# SensorNodePCB_set2_v2.net
KiCad netlist of a schematic drawn in EAGLE
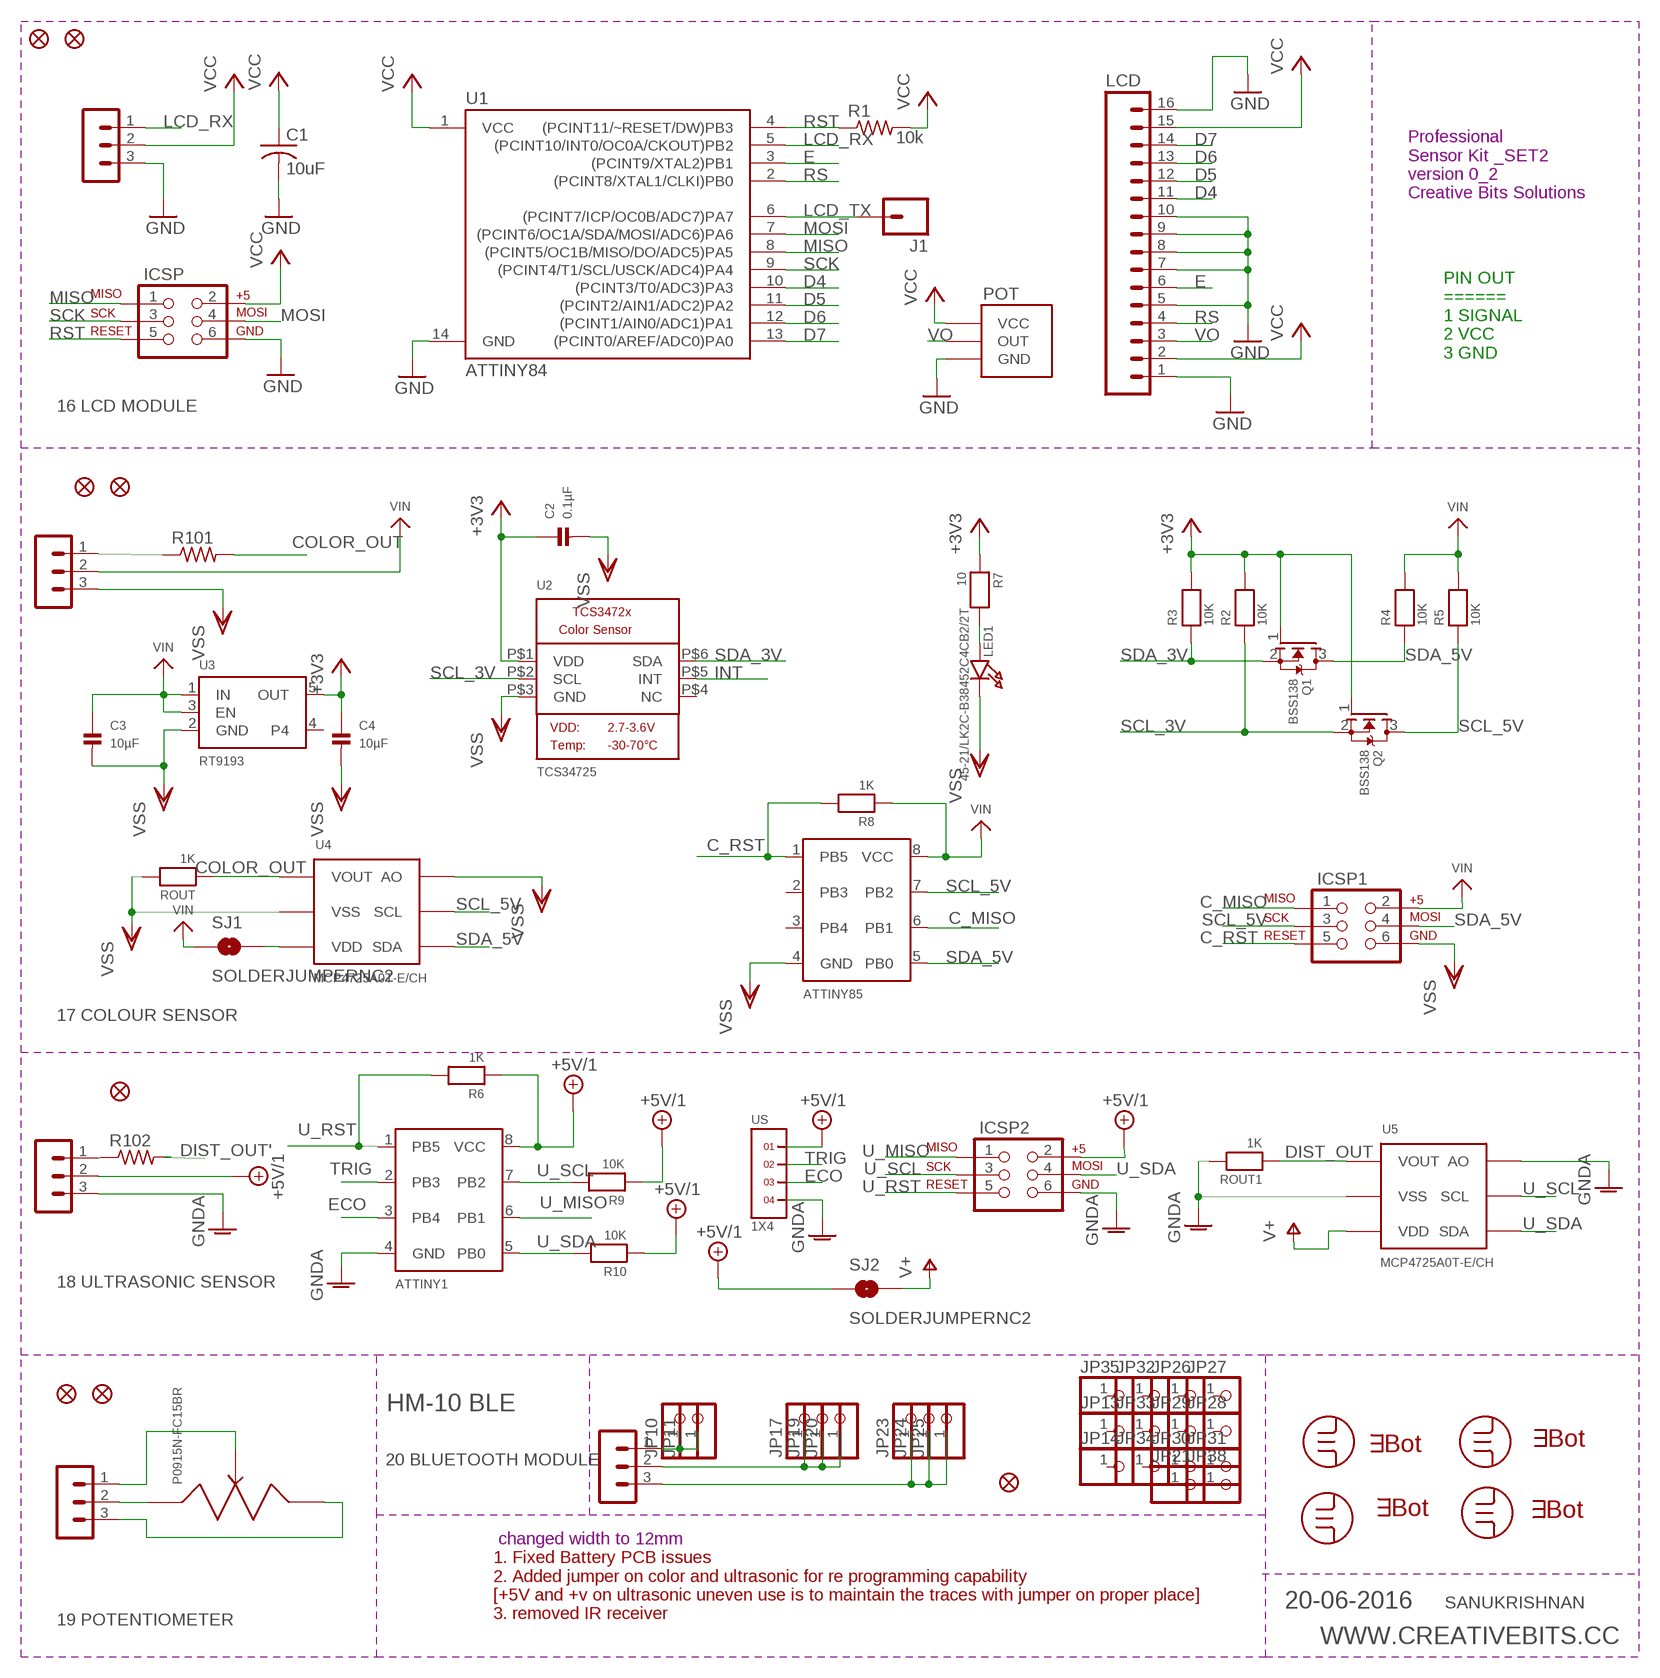
[diagram p0: schematic, sheet 1]

(export (version "E")
  (design (tool "Eeschema 10.0.6"))
  (components
    (comp (ref "ATTINY1")
      (value "ATTINY45")
      (footprint "eagle-import:SOIC8")
      (libsource (lib "eagle-import") (part "ATTINY45"))
    )
    (comp (ref "ATTINY85")
      (value "ATTINY45")
      (footprint "eagle-import:SOIC8")
      (libsource (lib "eagle-import") (part "ATTINY45"))
    )
    (comp (ref "C1")
      (value "10uF")
      (footprint "eagle-import:C1206")
      (libsource (lib "eagle-import") (part "C-USC1206"))
    )
    (comp (ref "C2")
      (value "0.1µF")
      (footprint "eagle-import:_0805")
      (libsource (lib "eagle-import") (part "CAP_CERAMIC_0805"))
    )
    (comp (ref "C3")
      (value "10µF")
      (footprint "eagle-import:_0805")
      (libsource (lib "eagle-import") (part "CAP_CERAMIC_0805"))
    )
    (comp (ref "C4")
      (value "10µF")
      (footprint "eagle-import:_0805")
      (libsource (lib "eagle-import") (part "CAP_CERAMIC_0805"))
    )
    (comp (ref "COLORSENSOR")
      (value "MA03-1")
      (footprint "eagle-import:MA03-1")
      (libsource (lib "eagle-import") (part "MA03-1"))
    )
    (comp (ref "ICSP")
      (value "AVR_SPI_PRG_6NS")
      (footprint "eagle-import:2X3-NS")
      (libsource (lib "eagle-import") (part "AVR_SPI_PRG_6NS"))
    )
    (comp (ref "ICSP1")
      (value "AVR_SPI_PRG_6NS")
      (footprint "eagle-import:2X3-NS")
      (libsource (lib "eagle-import") (part "AVR_SPI_PRG_6NS"))
    )
    (comp (ref "ICSP2")
      (value "AVR_SPI_PRG_6NS")
      (footprint "eagle-import:2X3-NS")
      (libsource (lib "eagle-import") (part "AVR_SPI_PRG_6NS"))
    )
    (comp (ref "J1")
      (value "M01NOSILK-KIT")
      (footprint "eagle-import:1X01NS-KIT")
      (libsource (lib "eagle-import") (part "M01NOSILK-KIT"))
    )
    (comp (ref "JP1")
      (value "FIDUCIAL1X2")
      (footprint "eagle-import:FIDUCIAL-1X2")
      (libsource (lib "eagle-import") (part "FIDUCIAL1X2"))
    )
    (comp (ref "JP2")
      (value "FIDUCIAL1X2")
      (footprint "eagle-import:FIDUCIAL-1X2")
      (libsource (lib "eagle-import") (part "FIDUCIAL1X2"))
    )
    (comp (ref "JP4")
      (value "FIDUCIAL1X2")
      (footprint "eagle-import:FIDUCIAL-1X2")
      (libsource (lib "eagle-import") (part "FIDUCIAL1X2"))
    )
    (comp (ref "JP6")
      (value "FIDUCIAL1X2")
      (footprint "eagle-import:FIDUCIAL-1X2")
      (libsource (lib "eagle-import") (part "FIDUCIAL1X2"))
    )
    (comp (ref "JP9")
      (value "FIDUCIAL1X2")
      (footprint "eagle-import:FIDUCIAL-1X2")
      (libsource (lib "eagle-import") (part "FIDUCIAL1X2"))
    )
    (comp (ref "JP10")
      (value "PINHD-1X1CB")
      (footprint "eagle-import:1X01-CLEANBIG")
      (libsource (lib "eagle-import") (part "PINHD-1X1CB"))
    )
    (comp (ref "JP11")
      (value "PINHD-1X1CB")
      (footprint "eagle-import:1X01-CLEANBIG")
      (libsource (lib "eagle-import") (part "PINHD-1X1CB"))
    )
    (comp (ref "JP12")
      (value "FIDUCIAL1X2")
      (footprint "eagle-import:FIDUCIAL-1X2")
      (libsource (lib "eagle-import") (part "FIDUCIAL1X2"))
    )
    (comp (ref "JP13")
      (value "PINHD-1X1CB")
      (footprint "eagle-import:1X01-CLEANBIG")
      (libsource (lib "eagle-import") (part "PINHD-1X1CB"))
    )
    (comp (ref "JP14")
      (value "PINHD-1X1CB")
      (footprint "eagle-import:1X01-CLEANBIG")
      (libsource (lib "eagle-import") (part "PINHD-1X1CB"))
    )
    (comp (ref "JP15")
      (value "FIDUCIAL1X2")
      (footprint "eagle-import:FIDUCIAL-1X2")
      (libsource (lib "eagle-import") (part "FIDUCIAL1X2"))
    )
    (comp (ref "JP17")
      (value "PINHD-1X1CB")
      (footprint "eagle-import:1X01-CLEANBIG")
      (libsource (lib "eagle-import") (part "PINHD-1X1CB"))
    )
    (comp (ref "JP18")
      (value "FIDUCIAL1X2")
      (footprint "eagle-import:FIDUCIAL-1X2")
      (libsource (lib "eagle-import") (part "FIDUCIAL1X2"))
    )
    (comp (ref "JP19")
      (value "PINHD-1X1CB")
      (footprint "eagle-import:1X01-CLEANBIG")
      (libsource (lib "eagle-import") (part "PINHD-1X1CB"))
    )
    (comp (ref "JP20")
      (value "PINHD-1X1CB")
      (footprint "eagle-import:1X01-CLEANBIG")
      (libsource (lib "eagle-import") (part "PINHD-1X1CB"))
    )
    (comp (ref "JP21")
      (value "PINHD-1X1CB")
      (footprint "eagle-import:1X01-CLEANBIG")
      (libsource (lib "eagle-import") (part "PINHD-1X1CB"))
    )
    (comp (ref "JP23")
      (value "PINHD-1X1CB")
      (footprint "eagle-import:1X01-CLEANBIG")
      (libsource (lib "eagle-import") (part "PINHD-1X1CB"))
    )
    (comp (ref "JP24")
      (value "PINHD-1X1CB")
      (footprint "eagle-import:1X01-CLEANBIG")
      (libsource (lib "eagle-import") (part "PINHD-1X1CB"))
    )
    (comp (ref "JP25")
      (value "PINHD-1X1CB")
      (footprint "eagle-import:1X01-CLEANBIG")
      (libsource (lib "eagle-import") (part "PINHD-1X1CB"))
    )
    (comp (ref "JP26")
      (value "PINHD-1X1CB")
      (footprint "eagle-import:1X01-CLEANBIG")
      (libsource (lib "eagle-import") (part "PINHD-1X1CB"))
    )
    (comp (ref "JP27")
      (value "PINHD-1X1CB")
      (footprint "eagle-import:1X01-CLEANBIG")
      (libsource (lib "eagle-import") (part "PINHD-1X1CB"))
    )
    (comp (ref "JP28")
      (value "PINHD-1X1CB")
      (footprint "eagle-import:1X01-CLEANBIG")
      (libsource (lib "eagle-import") (part "PINHD-1X1CB"))
    )
    (comp (ref "JP29")
      (value "PINHD-1X1CB")
      (footprint "eagle-import:1X01-CLEANBIG")
      (libsource (lib "eagle-import") (part "PINHD-1X1CB"))
    )
    (comp (ref "JP30")
      (value "PINHD-1X1CB")
      (footprint "eagle-import:1X01-CLEANBIG")
      (libsource (lib "eagle-import") (part "PINHD-1X1CB"))
    )
    (comp (ref "JP31")
      (value "PINHD-1X1CB")
      (footprint "eagle-import:1X01-CLEANBIG")
      (libsource (lib "eagle-import") (part "PINHD-1X1CB"))
    )
    (comp (ref "JP32")
      (value "PINHD-1X1CB")
      (footprint "eagle-import:1X01-CLEANBIG")
      (libsource (lib "eagle-import") (part "PINHD-1X1CB"))
    )
    (comp (ref "JP33")
      (value "PINHD-1X1CB")
      (footprint "eagle-import:1X01-CLEANBIG")
      (libsource (lib "eagle-import") (part "PINHD-1X1CB"))
    )
    (comp (ref "JP34")
      (value "PINHD-1X1CB")
      (footprint "eagle-import:1X01-CLEANBIG")
      (libsource (lib "eagle-import") (part "PINHD-1X1CB"))
    )
    (comp (ref "JP35")
      (value "PINHD-1X1CB")
      (footprint "eagle-import:1X01-CLEANBIG")
      (libsource (lib "eagle-import") (part "PINHD-1X1CB"))
    )
    (comp (ref "JP38")
      (value "PINHD-1X1CB")
      (footprint "eagle-import:1X01-CLEANBIG")
      (libsource (lib "eagle-import") (part "PINHD-1X1CB"))
    )
    (comp (ref "LCD")
      (value "M16LONGPADS")
      (footprint "eagle-import:1X16_LONGPADS")
      (libsource (lib "eagle-import") (part "M16LONGPADS"))
    )
    (comp (ref "LCD_NODE")
      (value "MA03-1")
      (footprint "eagle-import:MA03-1")
      (libsource (lib "eagle-import") (part "MA03-1"))
    )
    (comp (ref "LED1")
      (value "45-21/LK2C-B38452C4CB2/2T")
      (footprint "eagle-import:EVERLIGHT_45-21")
      (libsource (lib "eagle-import") (part "LEDEV45-21"))
    )
    (comp (ref "POT")
      (value "TRIMMER_EVN")
      (footprint "eagle-import:TRIMMER_EVN")
      (libsource (lib "eagle-import") (part "TRIMMER_EVN"))
    )
    (comp (ref "POT1")
      (value "P0915N-FC15BR")
      (footprint "eagle-import:P0915N-FC15BR")
      (libsource (lib "eagle-import") (part "P0915N-FC15BR"))
    )
    (comp (ref "POTENTIOMETER")
      (value "MA03-1")
      (footprint "eagle-import:MA03-1")
      (libsource (lib "eagle-import") (part "MA03-1"))
    )
    (comp (ref "Q1")
      (value "BSS138")
      (footprint "eagle-import:SOT23-WIDE")
      (libsource (lib "eagle-import") (part "MOSFET-NWIDE"))
    )
    (comp (ref "Q2")
      (value "BSS138")
      (footprint "eagle-import:SOT23-WIDE")
      (libsource (lib "eagle-import") (part "MOSFET-NWIDE"))
    )
    (comp (ref "R1")
      (value "10k")
      (footprint "eagle-import:M0805")
      (libsource (lib "eagle-import") (part "R-US_M0805"))
    )
    (comp (ref "R2")
      (value "10K")
      (footprint "eagle-import:_0805")
      (libsource (lib "eagle-import") (part "RESISTOR_0805"))
    )
    (comp (ref "R3")
      (value "10K")
      (footprint "eagle-import:_0805")
      (libsource (lib "eagle-import") (part "RESISTOR_0805"))
    )
    (comp (ref "R4")
      (value "10K")
      (footprint "eagle-import:_0805")
      (libsource (lib "eagle-import") (part "RESISTOR_0805"))
    )
    (comp (ref "R5")
      (value "10K")
      (footprint "eagle-import:_0805")
      (libsource (lib "eagle-import") (part "RESISTOR_0805"))
    )
    (comp (ref "R6")
      (value "1K")
      (footprint "eagle-import:_0805")
      (libsource (lib "eagle-import") (part "RESISTOR_0805"))
    )
    (comp (ref "R7")
      (value "10")
      (footprint "eagle-import:_0805")
      (libsource (lib "eagle-import") (part "RESISTOR_0805"))
    )
    (comp (ref "R8")
      (value "1K")
      (footprint "eagle-import:_0805")
      (libsource (lib "eagle-import") (part "RESISTOR_0805"))
    )
    (comp (ref "R9")
      (value "10K")
      (footprint "eagle-import:_0805")
      (libsource (lib "eagle-import") (part "RESISTOR_0805"))
    )
    (comp (ref "R10")
      (value "10K")
      (footprint "eagle-import:_0805")
      (libsource (lib "eagle-import") (part "RESISTOR_0805"))
    )
    (comp (ref "R101")
      (value "R-US_M0805")
      (footprint "eagle-import:M0805")
      (libsource (lib "eagle-import") (part "R-US_M0805"))
    )
    (comp (ref "R102")
      (value "R-US_M0805")
      (footprint "eagle-import:M0805")
      (libsource (lib "eagle-import") (part "R-US_M0805"))
    )
    (comp (ref "ROUT")
      (value "1K")
      (footprint "eagle-import:_0805")
      (libsource (lib "eagle-import") (part "RESISTOR_0805"))
    )
    (comp (ref "ROUT1")
      (value "1K")
      (footprint "eagle-import:_0805")
      (libsource (lib "eagle-import") (part "RESISTOR_0805"))
    )
    (comp (ref "SJ1")
      (value "SOLDERJUMPERNC2")
      (footprint "eagle-import:SJ_2S-NOTRACE")
      (libsource (lib "eagle-import") (part "SOLDERJUMPERNC2"))
    )
    (comp (ref "SJ2")
      (value "SOLDERJUMPERNC2")
      (footprint "eagle-import:SJ_2S-NOTRACE")
      (libsource (lib "eagle-import") (part "SOLDERJUMPERNC2"))
    )
    (comp (ref "U$30")
      (value "EBOT_LOGO_6MMX6MM")
      (footprint "eagle-import:EBOT_6MMX6MM")
      (libsource (lib "eagle-import") (part "EBOT_LOGO_6MMX6MM"))
    )
    (comp (ref "U$32")
      (value "EBOT_LOGO_6MMX6MM")
      (footprint "eagle-import:EBOT_6MMX6MM")
      (libsource (lib "eagle-import") (part "EBOT_LOGO_6MMX6MM"))
    )
    (comp (ref "U$33")
      (value "EBOT_LOGO_6MMX6MM")
      (footprint "eagle-import:EBOT_6MMX6MM")
      (libsource (lib "eagle-import") (part "EBOT_LOGO_6MMX6MM"))
    )
    (comp (ref "U$34")
      (value "EBOT_LOGO_6MMX6MM")
      (footprint "eagle-import:EBOT_6MMX6MM")
      (libsource (lib "eagle-import") (part "EBOT_LOGO_6MMX6MM"))
    )
    (comp (ref "U$35")
      (value "EBOT_NAME_6MM")
      (footprint "eagle-import:EBOT_NAME_6MM")
      (libsource (lib "eagle-import") (part "EBOT_NAME_6MM"))
    )
    (comp (ref "U$37")
      (value "EBOT_NAME_6MM")
      (footprint "eagle-import:EBOT_NAME_6MM")
      (libsource (lib "eagle-import") (part "EBOT_NAME_6MM"))
    )
    (comp (ref "U$38")
      (value "EBOT_NAME_6MM")
      (footprint "eagle-import:EBOT_NAME_6MM")
      (libsource (lib "eagle-import") (part "EBOT_NAME_6MM"))
    )
    (comp (ref "U$39")
      (value "EBOT_NAME_6MM")
      (footprint "eagle-import:EBOT_NAME_6MM")
      (libsource (lib "eagle-import") (part "EBOT_NAME_6MM"))
    )
    (comp (ref "U1")
      (value "ATTINY84")
      (footprint "eagle-import:SO14")
      (libsource (lib "eagle-import") (part "ATTINY84"))
    )
    (comp (ref "U2")
      (value "TCS34725")
      (footprint "eagle-import:TCS3472_FN6")
      (libsource (lib "eagle-import") (part "LIGHT_TCS3472"))
    )
    (comp (ref "U3")
      (value "RT9193")
      (footprint "eagle-import:SOT23-5")
      (libsource (lib "eagle-import") (part "VREG_SOT23-5"))
    )
    (comp (ref "U4")
      (value "MCP4725")
      (footprint "eagle-import:MCP4725")
      (libsource (lib "eagle-import") (part "MCP4725"))
    )
    (comp (ref "U5")
      (value "MCP4725")
      (footprint "eagle-import:MCP4725")
      (libsource (lib "eagle-import") (part "MCP4725"))
    )
    (comp (ref "ULTRASONICSENSOR")
      (value "MA03-1")
      (footprint "eagle-import:MA03-1")
      (libsource (lib "eagle-import") (part "MA03-1"))
    )
    (comp (ref "ULTRASONICSENSOR1")
      (value "MA03-1")
      (footprint "eagle-import:MA03-1")
      (libsource (lib "eagle-import") (part "MA03-1"))
    )
    (comp (ref "US")
      (value "1X4")
      (footprint "eagle-import:1X4")
      (libsource (lib "eagle-import") (part "1X4"))
    )
  )
  (nets
    (net (code "1") (name "+3V3") (class "Default")
      (node (ref "C2") (pin "1") (pinfunction "P$1_1") (pintype "passive"))
      (node (ref "C4") (pin "1") (pinfunction "P$1_1") (pintype "passive"))
      (node (ref "Q1") (pin "1") (pinfunction "G_1") (pintype "bidirectional"))
      (node (ref "Q2") (pin "1") (pinfunction "G_1") (pintype "bidirectional"))
      (node (ref "R2") (pin "2") (pinfunction "2_2") (pintype "passive"))
      (node (ref "R3") (pin "2") (pinfunction "2_2") (pintype "passive"))
      (node (ref "R7") (pin "1") (pinfunction "1_1") (pintype "passive"))
      (node (ref "U2") (pin "P$1") (pinfunction "VDD_P$1") (pintype "power_in"))
      (node (ref "U3") (pin "5") (pinfunction "OUT_5") (pintype "bidirectional"))
    )
    (net (code "2") (name "+5V{slash}1") (class "Default")
      (node (ref "ATTINY1") (pin "8") (pinfunction "VCC_8") (pintype "power_in"))
      (node (ref "ICSP2") (pin "2") (pinfunction "2_2") (pintype "passive"))
      (node (ref "R10") (pin "1") (pinfunction "1_1") (pintype "passive"))
      (node (ref "R6") (pin "1") (pinfunction "1_1") (pintype "passive"))
      (node (ref "R9") (pin "1") (pinfunction "1_1") (pintype "passive"))
      (node (ref "SJ2") (pin "1") (pinfunction "1_1") (pintype "passive"))
      (node (ref "ULTRASONICSENSOR") (pin "2") (pinfunction "2_2") (pintype "passive"))
      (node (ref "US") (pin "1") (pinfunction "1_1") (pintype "bidirectional"))
    )
    (net (code "3") (name "/COLOR_OUT") (class "Default")
      (node (ref "R101") (pin "2") (pinfunction "2_2") (pintype "passive"))
      (node (ref "ROUT") (pin "1") (pinfunction "1_1") (pintype "passive"))
      (node (ref "U4") (pin "P$1") (pinfunction "VOUT_P$1") (pintype "bidirectional"))
    )
    (net (code "4") (name "/C_MISO") (class "Default")
      (node (ref "ATTINY85") (pin "6") (pinfunction "PB1_6") (pintype "bidirectional"))
      (node (ref "ICSP1") (pin "1") (pinfunction "1_1") (pintype "passive"))
    )
    (net (code "5") (name "/C_RST") (class "Default")
      (node (ref "ATTINY85") (pin "1") (pinfunction "PB5_1") (pintype "bidirectional"))
      (node (ref "ICSP1") (pin "5") (pinfunction "5_5") (pintype "passive"))
      (node (ref "R8") (pin "2") (pinfunction "2_2") (pintype "passive"))
    )
    (net (code "6") (name "/D4") (class "Default")
      (node (ref "LCD") (pin "11") (pinfunction "11_11") (pintype "passive"))
      (node (ref "U1") (pin "10") (pinfunction "(PCINT3/T0/ADC3)PA3_10") (pintype "bidirectional"))
    )
    (net (code "7") (name "/D5") (class "Default")
      (node (ref "LCD") (pin "12") (pinfunction "12_12") (pintype "passive"))
      (node (ref "U1") (pin "11") (pinfunction "(PCINT2/AIN1/ADC2)PA2_11") (pintype "bidirectional"))
    )
    (net (code "8") (name "/D6") (class "Default")
      (node (ref "LCD") (pin "13") (pinfunction "13_13") (pintype "passive"))
      (node (ref "U1") (pin "12") (pinfunction "(PCINT1/AIN0/ADC1)PA1_12") (pintype "bidirectional"))
    )
    (net (code "9") (name "/D7") (class "Default")
      (node (ref "LCD") (pin "14") (pinfunction "14_14") (pintype "passive"))
      (node (ref "U1") (pin "13") (pinfunction "(PCINT0/AREF/ADC0)PA0_13") (pintype "bidirectional"))
    )
    (net (code "10") (name "/DIST_OUT") (class "Default")
      (node (ref "R102") (pin "2") (pinfunction "2_2") (pintype "passive"))
      (node (ref "ROUT1") (pin "1") (pinfunction "1_1") (pintype "passive"))
      (node (ref "U5") (pin "P$1") (pinfunction "VOUT_P$1") (pintype "bidirectional"))
    )
    (net (code "11") (name "/DIST_OUT'") (class "Default")
      (node (ref "R102") (pin "1") (pinfunction "1_1") (pintype "passive"))
      (node (ref "ULTRASONICSENSOR") (pin "1") (pinfunction "1_1") (pintype "passive"))
    )
    (net (code "12") (name "/E") (class "Default")
      (node (ref "LCD") (pin "6") (pinfunction "6_6") (pintype "passive"))
      (node (ref "U1") (pin "3") (pinfunction "(PCINT9/XTAL2)PB1_3") (pintype "bidirectional"))
    )
    (net (code "13") (name "/ECO") (class "Default")
      (node (ref "ATTINY1") (pin "3") (pinfunction "PB4_3") (pintype "bidirectional"))
      (node (ref "US") (pin "3") (pinfunction "3_3") (pintype "bidirectional"))
    )
    (net (code "14") (name "/INT") (class "Default")
      (node (ref "U2") (pin "P$5") (pinfunction "INT_P$5") (pintype "output"))
    )
    (net (code "15") (name "/LCD_RX") (class "Default")
      (node (ref "LCD_NODE") (pin "1") (pinfunction "1_1") (pintype "passive"))
      (node (ref "U1") (pin "5") (pinfunction "(PCINT10/INT0/OC0A/CKOUT)PB2_5") (pintype "bidirectional"))
    )
    (net (code "16") (name "/LCD_TX") (class "Default")
      (node (ref "J1") (pin "1") (pinfunction "1_1") (pintype "passive"))
      (node (ref "U1") (pin "6") (pinfunction "(PCINT7/ICP/OC0B/ADC7)PA7_6") (pintype "bidirectional"))
    )
    (net (code "17") (name "/MISO") (class "Default")
      (node (ref "ICSP") (pin "1") (pinfunction "1_1") (pintype "passive"))
      (node (ref "U1") (pin "8") (pinfunction "(PCINT5/OC1B/MISO/DO/ADC5)PA5_8") (pintype "bidirectional"))
    )
    (net (code "18") (name "/MOSI") (class "Default")
      (node (ref "ICSP") (pin "4") (pinfunction "4_4") (pintype "passive"))
      (node (ref "U1") (pin "7") (pinfunction "(PCINT6/OC1A/SDA/MOSI/ADC6)PA6_7") (pintype "bidirectional"))
    )
    (net (code "19") (name "/RS") (class "Default")
      (node (ref "LCD") (pin "4") (pinfunction "4_4") (pintype "passive"))
      (node (ref "U1") (pin "2") (pinfunction "(PCINT8/XTAL1/CLKI)PB0_2") (pintype "bidirectional"))
    )
    (net (code "20") (name "/RST") (class "Default")
      (node (ref "ICSP") (pin "5") (pinfunction "5_5") (pintype "passive"))
      (node (ref "R1") (pin "1") (pinfunction "1_1") (pintype "passive"))
      (node (ref "U1") (pin "4") (pinfunction "(PCINT11/~{RESET/DW})PB3_4") (pintype "bidirectional"))
    )
    (net (code "21") (name "/SCK") (class "Default")
      (node (ref "ICSP") (pin "3") (pinfunction "3_3") (pintype "passive"))
      (node (ref "U1") (pin "9") (pinfunction "(PCINT4/T1/SCL/USCK/ADC4)PA4_9") (pintype "bidirectional"))
    )
    (net (code "22") (name "/SCL_3V") (class "Default")
      (node (ref "Q2") (pin "2") (pinfunction "S_2") (pintype "bidirectional"))
      (node (ref "R2") (pin "1") (pinfunction "1_1") (pintype "passive"))
      (node (ref "U2") (pin "P$2") (pinfunction "SCL_P$2") (pintype "bidirectional"))
    )
    (net (code "23") (name "/SCL_5V") (class "Default")
      (node (ref "ATTINY85") (pin "7") (pinfunction "PB2_7") (pintype "bidirectional"))
      (node (ref "ICSP1") (pin "3") (pinfunction "3_3") (pintype "passive"))
      (node (ref "Q2") (pin "3") (pinfunction "D_3") (pintype "bidirectional"))
      (node (ref "R5") (pin "1") (pinfunction "1_1") (pintype "passive"))
      (node (ref "U4") (pin "P$5") (pinfunction "SCL_P$5") (pintype "bidirectional"))
    )
    (net (code "24") (name "/SDA_3V") (class "Default")
      (node (ref "Q1") (pin "2") (pinfunction "S_2") (pintype "bidirectional"))
      (node (ref "R3") (pin "1") (pinfunction "1_1") (pintype "passive"))
      (node (ref "U2") (pin "P$6") (pinfunction "SDA_P$6") (pintype "bidirectional"))
    )
    (net (code "25") (name "/SDA_5V") (class "Default")
      (node (ref "ATTINY85") (pin "5") (pinfunction "PB0_5") (pintype "bidirectional"))
      (node (ref "ICSP1") (pin "4") (pinfunction "4_4") (pintype "passive"))
      (node (ref "Q1") (pin "3") (pinfunction "D_3") (pintype "bidirectional"))
      (node (ref "R4") (pin "1") (pinfunction "1_1") (pintype "passive"))
      (node (ref "U4") (pin "P$4") (pinfunction "SDA_P$4") (pintype "bidirectional"))
    )
    (net (code "26") (name "/TRIG") (class "Default")
      (node (ref "ATTINY1") (pin "2") (pinfunction "PB3_2") (pintype "bidirectional"))
      (node (ref "US") (pin "2") (pinfunction "2_2") (pintype "bidirectional"))
    )
    (net (code "27") (name "/U_MISO") (class "Default")
      (node (ref "ATTINY1") (pin "6") (pinfunction "PB1_6") (pintype "bidirectional"))
      (node (ref "ICSP2") (pin "1") (pinfunction "1_1") (pintype "passive"))
    )
    (net (code "28") (name "/U_RST") (class "Default")
      (node (ref "ATTINY1") (pin "1") (pinfunction "PB5_1") (pintype "bidirectional"))
      (node (ref "ICSP2") (pin "5") (pinfunction "5_5") (pintype "passive"))
      (node (ref "R6") (pin "2") (pinfunction "2_2") (pintype "passive"))
    )
    (net (code "29") (name "/U_SCL") (class "Default")
      (node (ref "ATTINY1") (pin "7") (pinfunction "PB2_7") (pintype "bidirectional"))
      (node (ref "ICSP2") (pin "3") (pinfunction "3_3") (pintype "passive"))
      (node (ref "R9") (pin "2") (pinfunction "2_2") (pintype "passive"))
      (node (ref "U5") (pin "P$5") (pinfunction "SCL_P$5") (pintype "bidirectional"))
    )
    (net (code "30") (name "/U_SDA") (class "Default")
      (node (ref "ATTINY1") (pin "5") (pinfunction "PB0_5") (pintype "bidirectional"))
      (node (ref "ICSP2") (pin "4") (pinfunction "4_4") (pintype "passive"))
      (node (ref "R10") (pin "2") (pinfunction "2_2") (pintype "passive"))
      (node (ref "U5") (pin "P$4") (pinfunction "SDA_P$4") (pintype "bidirectional"))
    )
    (net (code "31") (name "/VO") (class "Default")
      (node (ref "LCD") (pin "3") (pinfunction "3_3") (pintype "passive"))
      (node (ref "POT") (pin "P$3") (pinfunction "OUT_P$3") (pintype "bidirectional"))
    )
    (net (code "32") (name "GND") (class "Default")
      (node (ref "C1") (pin "2") (pinfunction "2_2") (pintype "passive"))
      (node (ref "ICSP") (pin "6") (pinfunction "6_6") (pintype "passive"))
      (node (ref "LCD") (pin "1") (pinfunction "1_1") (pintype "passive"))
      (node (ref "LCD") (pin "10") (pinfunction "10_10") (pintype "passive"))
      (node (ref "LCD") (pin "16") (pinfunction "16_16") (pintype "passive"))
      (node (ref "LCD") (pin "5") (pinfunction "5_5") (pintype "passive"))
      (node (ref "LCD") (pin "7") (pinfunction "7_7") (pintype "passive"))
      (node (ref "LCD") (pin "8") (pinfunction "8_8") (pintype "passive"))
      (node (ref "LCD") (pin "9") (pinfunction "9_9") (pintype "passive"))
      (node (ref "LCD_NODE") (pin "3") (pinfunction "3_3") (pintype "passive"))
      (node (ref "POT") (pin "P$2") (pinfunction "GND_P$2") (pintype "bidirectional"))
      (node (ref "U1") (pin "14") (pinfunction "GND_14") (pintype "bidirectional"))
    )
    (net (code "33") (name "GNDA") (class "Default")
      (node (ref "ATTINY1") (pin "4") (pinfunction "GND_4") (pintype "power_in"))
      (node (ref "ICSP2") (pin "6") (pinfunction "6_6") (pintype "passive"))
      (node (ref "ROUT1") (pin "2") (pinfunction "2_2") (pintype "passive"))
      (node (ref "U5") (pin "P$2") (pinfunction "VSS_P$2") (pintype "bidirectional"))
      (node (ref "U5") (pin "P$6") (pinfunction "AO_P$6") (pintype "bidirectional"))
      (node (ref "ULTRASONICSENSOR") (pin "3") (pinfunction "3_3") (pintype "passive"))
      (node (ref "US") (pin "4") (pinfunction "4_4") (pintype "bidirectional"))
    )
    (net (code "34") (name "Net-(COLORSENSOR-Pad1)") (class "Default")
      (node (ref "COLORSENSOR") (pin "1") (pinfunction "1_1") (pintype "passive"))
      (node (ref "R101") (pin "1") (pinfunction "1_1") (pintype "passive"))
    )
    (net (code "35") (name "Net-(JP10-Pad1)") (class "Default")
      (node (ref "JP10") (pin "1") (pinfunction "1_1") (pintype "passive"))
      (node (ref "JP11") (pin "1") (pinfunction "1_1") (pintype "passive"))
      (node (ref "ULTRASONICSENSOR1") (pin "1") (pinfunction "1_1") (pintype "passive"))
    )
    (net (code "36") (name "Net-(JP17-Pad1)") (class "Default")
      (node (ref "JP17") (pin "1") (pinfunction "1_1") (pintype "passive"))
      (node (ref "JP19") (pin "1") (pinfunction "1_1") (pintype "passive"))
      (node (ref "JP20") (pin "1") (pinfunction "1_1") (pintype "passive"))
      (node (ref "ULTRASONICSENSOR1") (pin "2") (pinfunction "2_2") (pintype "passive"))
    )
    (net (code "37") (name "Net-(JP23-Pad1)") (class "Default")
      (node (ref "JP23") (pin "1") (pinfunction "1_1") (pintype "passive"))
      (node (ref "JP24") (pin "1") (pinfunction "1_1") (pintype "passive"))
      (node (ref "JP25") (pin "1") (pinfunction "1_1") (pintype "passive"))
      (node (ref "ULTRASONICSENSOR1") (pin "3") (pinfunction "3_3") (pintype "passive"))
    )
    (net (code "38") (name "Net-(LED1-PadA)") (class "Default")
      (node (ref "LED1") (pin "A") (pinfunction "A_A") (pintype "passive"))
      (node (ref "R7") (pin "2") (pinfunction "2_2") (pintype "passive"))
    )
    (net (code "39") (name "Net-(POT1-PadGND)") (class "Default")
      (node (ref "POT1") (pin "GND") (pinfunction "GND_GND") (pintype "bidirectional"))
      (node (ref "POTENTIOMETER") (pin "3") (pinfunction "3_3") (pintype "passive"))
    )
    (net (code "40") (name "Net-(POT1-PadOUT)") (class "Default")
      (node (ref "POT1") (pin "OUT") (pinfunction "OUT_OUT") (pintype "bidirectional"))
      (node (ref "POTENTIOMETER") (pin "1") (pinfunction "1_1") (pintype "passive"))
    )
    (net (code "41") (name "Net-(POT1-PadVCC)") (class "Default")
      (node (ref "POT1") (pin "VCC") (pinfunction "VCC_VCC") (pintype "bidirectional"))
      (node (ref "POTENTIOMETER") (pin "2") (pinfunction "2_2") (pintype "passive"))
    )
    (net (code "42") (name "Net-(U4-VDD)") (class "Default")
      (node (ref "SJ1") (pin "2") (pinfunction "2_2") (pintype "passive"))
      (node (ref "U4") (pin "P$3") (pinfunction "VDD_P$3") (pintype "bidirectional"))
    )
    (net (code "43") (name "V+") (class "Default")
      (node (ref "SJ2") (pin "2") (pinfunction "2_2") (pintype "passive"))
      (node (ref "U5") (pin "P$3") (pinfunction "VDD_P$3") (pintype "bidirectional"))
    )
    (net (code "44") (name "VCC") (class "Default")
      (node (ref "C1") (pin "1") (pinfunction "1_1") (pintype "passive"))
      (node (ref "ICSP") (pin "2") (pinfunction "2_2") (pintype "passive"))
      (node (ref "LCD") (pin "15") (pinfunction "15_15") (pintype "passive"))
      (node (ref "LCD") (pin "2") (pinfunction "2_2") (pintype "passive"))
      (node (ref "LCD_NODE") (pin "2") (pinfunction "2_2") (pintype "passive"))
      (node (ref "POT") (pin "P$1") (pinfunction "VCC_P$1") (pintype "power_in"))
      (node (ref "R1") (pin "2") (pinfunction "2_2") (pintype "passive"))
      (node (ref "U1") (pin "1") (pinfunction "VCC_1") (pintype "bidirectional"))
    )
    (net (code "45") (name "VIN") (class "Default")
      (node (ref "ATTINY85") (pin "8") (pinfunction "VCC_8") (pintype "power_in"))
      (node (ref "C3") (pin "1") (pinfunction "P$1_1") (pintype "passive"))
      (node (ref "COLORSENSOR") (pin "2") (pinfunction "2_2") (pintype "passive"))
      (node (ref "ICSP1") (pin "2") (pinfunction "2_2") (pintype "passive"))
      (node (ref "R4") (pin "2") (pinfunction "2_2") (pintype "passive"))
      (node (ref "R5") (pin "2") (pinfunction "2_2") (pintype "passive"))
      (node (ref "R8") (pin "1") (pinfunction "1_1") (pintype "passive"))
      (node (ref "SJ1") (pin "1") (pinfunction "1_1") (pintype "passive"))
      (node (ref "U3") (pin "1") (pinfunction "IN_1") (pintype "bidirectional"))
      (node (ref "U3") (pin "3") (pinfunction "EN_3") (pintype "bidirectional"))
    )
    (net (code "46") (name "VSS") (class "Default")
      (node (ref "ATTINY85") (pin "4") (pinfunction "GND_4") (pintype "power_in"))
      (node (ref "C2") (pin "2") (pinfunction "P$2_2") (pintype "passive"))
      (node (ref "C3") (pin "2") (pinfunction "P$2_2") (pintype "passive"))
      (node (ref "C4") (pin "2") (pinfunction "P$2_2") (pintype "passive"))
      (node (ref "COLORSENSOR") (pin "3") (pinfunction "3_3") (pintype "passive"))
      (node (ref "ICSP1") (pin "6") (pinfunction "6_6") (pintype "passive"))
      (node (ref "LED1") (pin "K") (pinfunction "C_K") (pintype "passive"))
      (node (ref "ROUT") (pin "2") (pinfunction "2_2") (pintype "passive"))
      (node (ref "U2") (pin "P$3") (pinfunction "GND_P$3") (pintype "power_in"))
      (node (ref "U3") (pin "2") (pinfunction "GND_2") (pintype "bidirectional"))
      (node (ref "U4") (pin "P$2") (pinfunction "VSS_P$2") (pintype "bidirectional"))
      (node (ref "U4") (pin "P$6") (pinfunction "AO_P$6") (pintype "bidirectional"))
    )
    (net (code "47") (name "unconnected-(ATTINY85-PB3-Pad2)") (class "Default")
      (node (ref "ATTINY85") (pin "2") (pinfunction "PB3_2") (pintype "bidirectional"))
    )
    (net (code "48") (name "unconnected-(ATTINY85-PB4-Pad3)") (class "Default")
      (node (ref "ATTINY85") (pin "3") (pinfunction "PB4_3") (pintype "bidirectional"))
    )
    (net (code "49") (name "unconnected-(JP13-Pad1)") (class "Default")
      (node (ref "JP13") (pin "1") (pinfunction "1_1") (pintype "passive"))
    )
    (net (code "50") (name "unconnected-(JP14-Pad1)") (class "Default")
      (node (ref "JP14") (pin "1") (pinfunction "1_1") (pintype "passive"))
    )
    (net (code "51") (name "unconnected-(JP21-Pad1)") (class "Default")
      (node (ref "JP21") (pin "1") (pinfunction "1_1") (pintype "passive"))
    )
    (net (code "52") (name "unconnected-(JP26-Pad1)") (class "Default")
      (node (ref "JP26") (pin "1") (pinfunction "1_1") (pintype "passive"))
    )
    (net (code "53") (name "unconnected-(JP27-Pad1)") (class "Default")
      (node (ref "JP27") (pin "1") (pinfunction "1_1") (pintype "passive"))
    )
    (net (code "54") (name "unconnected-(JP28-Pad1)") (class "Default")
      (node (ref "JP28") (pin "1") (pinfunction "1_1") (pintype "passive"))
    )
    (net (code "55") (name "unconnected-(JP29-Pad1)") (class "Default")
      (node (ref "JP29") (pin "1") (pinfunction "1_1") (pintype "passive"))
    )
    (net (code "56") (name "unconnected-(JP30-Pad1)") (class "Default")
      (node (ref "JP30") (pin "1") (pinfunction "1_1") (pintype "passive"))
    )
    (net (code "57") (name "unconnected-(JP31-Pad1)") (class "Default")
      (node (ref "JP31") (pin "1") (pinfunction "1_1") (pintype "passive"))
    )
    (net (code "58") (name "unconnected-(JP32-Pad1)") (class "Default")
      (node (ref "JP32") (pin "1") (pinfunction "1_1") (pintype "passive"))
    )
    (net (code "59") (name "unconnected-(JP33-Pad1)") (class "Default")
      (node (ref "JP33") (pin "1") (pinfunction "1_1") (pintype "passive"))
    )
    (net (code "60") (name "unconnected-(JP34-Pad1)") (class "Default")
      (node (ref "JP34") (pin "1") (pinfunction "1_1") (pintype "passive"))
    )
    (net (code "61") (name "unconnected-(JP35-Pad1)") (class "Default")
      (node (ref "JP35") (pin "1") (pinfunction "1_1") (pintype "passive"))
    )
    (net (code "62") (name "unconnected-(JP38-Pad1)") (class "Default")
      (node (ref "JP38") (pin "1") (pinfunction "1_1") (pintype "passive"))
    )
    (net (code "63") (name "unconnected-(U2-NC-PadP$4)") (class "Default")
      (node (ref "U2") (pin "P$4") (pinfunction "NC_P$4") (pintype "no_connect"))
    )
    (net (code "64") (name "unconnected-(U3-P4-Pad4)") (class "Default")
      (node (ref "U3") (pin "4") (pinfunction "P4_4") (pintype "bidirectional"))
    )
  )
)
